# MCU.net
KiCad netlist of a schematic drawn in Altium Designer
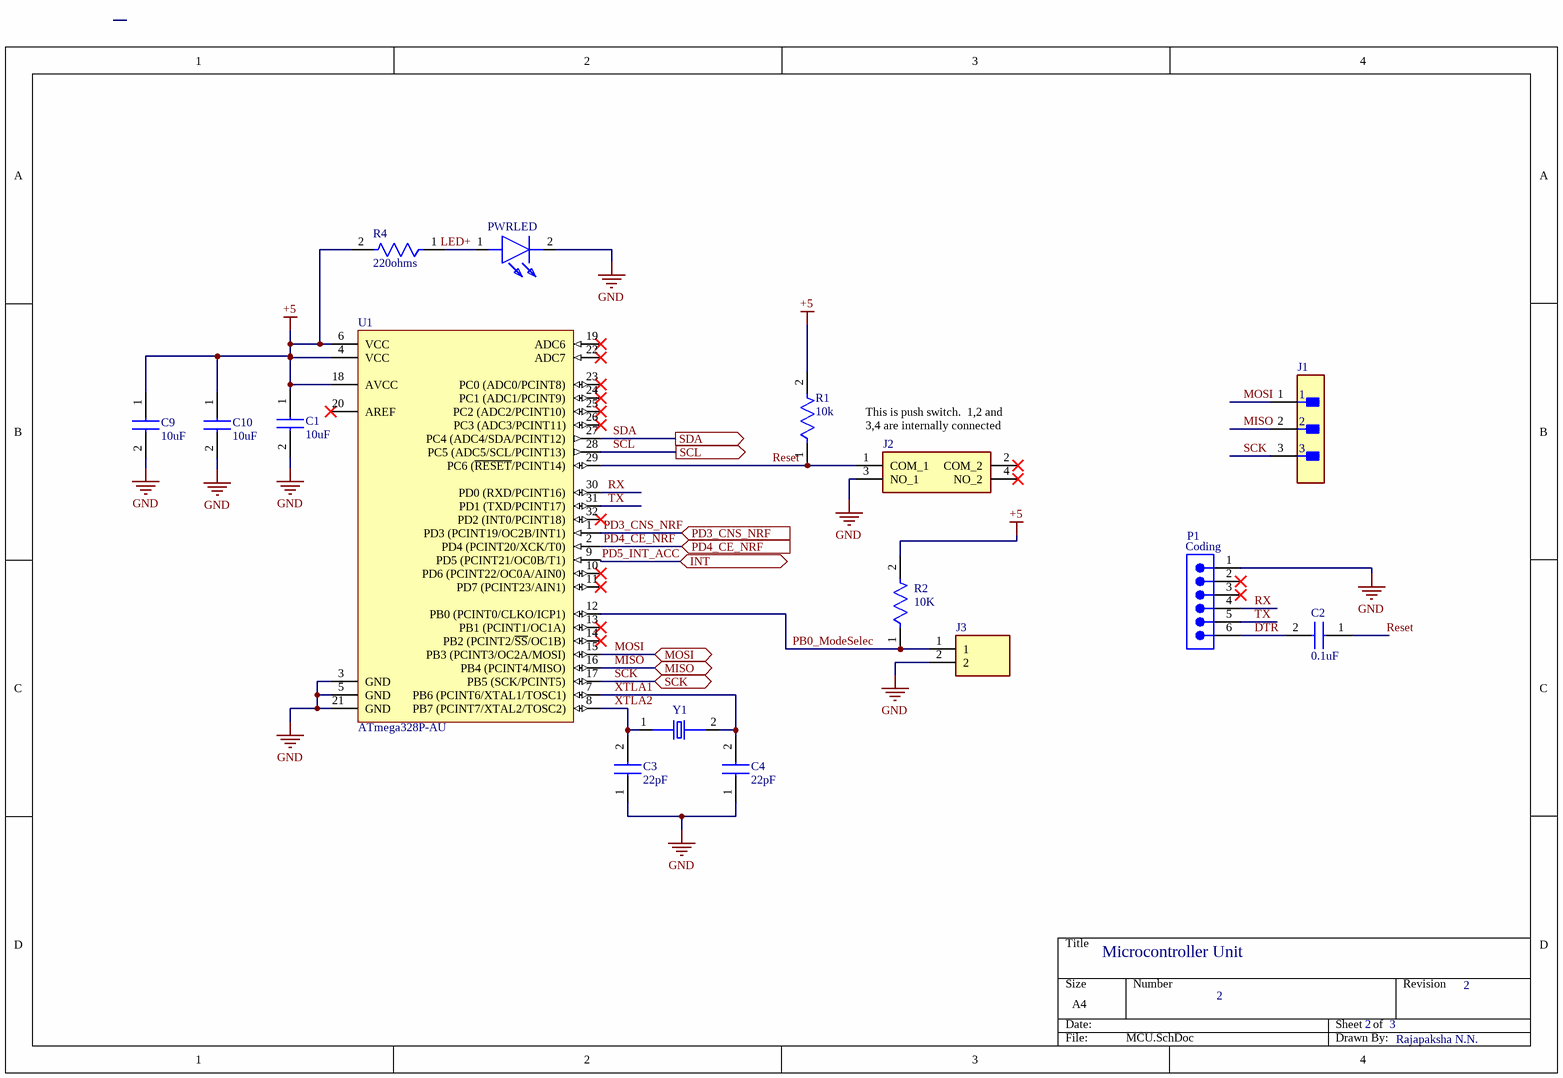
[diagram p0: MCU.SchDoc]

(export (version "E")
  (design (tool "Eeschema 10.0.6"))
  (components
    (comp (ref "C1")
      (value "10uF")
      (footprint "SamacSys:CAPC3216X180N")
      (description "Capacitor")
      (fields
        (field (name "MANUFACTURER_PART_NUMBER") "GRT31CR71E106KE13L")
        (field (name "MOUSER PART NUMBER") "81-GRT31CR71E106KE3L")
      )
      (libsource (lib "*") (part "GRT31CR71E106KE13L"))
    )
    (comp (ref "C2")
      (value "0.1uF")
      (footprint "SamacSys:C0805")
      (description "Capacitor")
      (fields
        (field (name "MANUFACTURER_PART_NUMBER") "C0805R104J5RACTU")
        (field (name "MOUSER PART NUMBER") "80-C0805R104J5RACTU")
      )
      (libsource (lib "*") (part "C0805R104J5RACTU"))
    )
    (comp (ref "C3")
      (value "22pF")
      (footprint "SamacSys:C0805")
      (description "Capacitor")
      (fields
        (field (name "MANUFACTURER_PART_NUMBER") "C0805C220F1HACTU")
        (field (name "MOUSER PART NUMBER") "80-C0805C220F1HACTU")
      )
      (libsource (lib "*") (part "C0805C220F1HACTU"))
    )
    (comp (ref "C4")
      (value "22pF")
      (footprint "SamacSys:C0805")
      (description "Capacitor")
      (fields
        (field (name "MANUFACTURER_PART_NUMBER") "C0805C220F1HACTU")
        (field (name "MOUSER PART NUMBER") "80-C0805C220F1HACTU")
      )
      (libsource (lib "*") (part "C0805C220F1HACTU"))
    )
    (comp (ref "C9")
      (value "10uF")
      (footprint "SamacSys:CAPC3216X180N")
      (description "Capacitor")
      (fields
        (field (name "MANUFACTURER_PART_NUMBER") "GRT31CR71E106KE13L")
        (field (name "MOUSER PART NUMBER") "81-GRT31CR71E106KE3L")
      )
      (libsource (lib "*") (part "GRT31CR71E106KE13L"))
    )
    (comp (ref "C10")
      (value "10uF")
      (footprint "SamacSys:CAPC3216X180N")
      (description "Capacitor")
      (fields
        (field (name "MANUFACTURER_PART_NUMBER") "GRT31CR71E106KE13L")
        (field (name "MOUSER PART NUMBER") "81-GRT31CR71E106KE3L")
      )
      (libsource (lib "*") (part "GRT31CR71E106KE13L"))
    )
    (comp (ref "J1")
      (value "87224-3")
      (footprint "FP-87224-3-MFG")
      (description "CONN HEADER VERT 3POS 2.54MM")
      (libsource (lib "Altium Content Vault") (part "0d3f023dd272f625e17a2be33dea85f"))
    )
    (comp (ref "J2")
      (value "8-1437565-1")
      (footprint "SamacSys:814375651")
      (description "Connector")
      (fields (field (name "MOUSER PART NUMBER") "506-8-1437565-1"))
      (libsource (lib "*") (part "8-1437565-1"))
    )
    (comp (ref "J3")
      (value "1727010")
      (footprint "SamacSys:1727010")
      (description "Connector")
      (fields (field (name "MOUSER PART NUMBER") "651-1727010"))
      (libsource (lib "*") (part "1727010"))
    )
    (comp (ref "P1")
      (value "Coding")
      (footprint "SMTC-TSW-106-07-X-S")
      (description "0.025\" SQ Post Header, Through-hole, Vertical, -55 to 125 degC, 2.54 mm Pitch, 6-Pin, Male, RoHS")
      (fields (field (name "PARTNUMBER") "TSW-106-07-L-S") (field (name "MANUFACTURER") "Samtec"))
      (libsource (lib "Altium Content Vault") (part "SMTC-TSW-106-X-X-S-X"))
    )
    (comp (ref "PWRLED")
      (value "598-2105-107F")
      (footprint "SamacSys:5982105107F")
      (description "LED")
      (fields (field (name "MOUSER PART NUMBER") "645-598-2105-107F"))
      (libsource (lib "*") (part "598-2105-107F"))
    )
    (comp (ref "R1")
      (value "10k")
      (footprint "FP-RK73H2A-IPC_C")
      (description "10kΩ ±1% 0.25W Chip Resistor 0805 Thick Film AEC-Q200 Qualified")
      (fields (field (name "TOLERANCE") "1%"))
      (libsource (lib "Altium Content Vault") (part "1029c3af85768c4190bb7ad29bc67b5"))
    )
    (comp (ref "R2")
      (value "10K")
      (footprint "FP-RK73H2A-IPC_C")
      (description "10kΩ ±1% 0.25W Chip Resistor 0805 Thick Film AEC-Q200 Qualified")
      (fields (field (name "TOLERANCE") "1%") (field (name "Comment") "10k"))
      (libsource (lib "Altium Content Vault") (part "1029c3af85768c4190bb7ad29bc67b5"))
    )
    (comp (ref "R4")
      (value "220ohms")
      (footprint "FP-RK73H2A-IPC_C")
      (description "10kΩ ±1% 0.25W Chip Resistor 0805 Thick Film AEC-Q200 Qualified")
      (fields (field (name "TOLERANCE") "1%"))
      (libsource (lib "Altium Content Vault") (part "1029c3af85768c4190bb7ad29bc67b5"))
    )
    (comp (ref "U1")
      (value "ATmega328P-AU")
      (footprint "32A_M")
      (libsource (lib "Altium Content Vault") (part "MC-8B-ATM48-SQ32"))
    )
    (comp (ref "Y1")
      (value "FOXSDLF/160-20")
      (footprint "XTAL_FOXSDLF/160-20")
      (description "Microprocessor, Crystal; 16 Mhz; + 30 Ppm @ Degc; 7 Pf (Max.); 20 Pf; -20 Deg")
      (fields (field (name "MF") "Fox Electronics"))
      (libsource (lib "FOXSDLF_160-20 (2)") (part "FOXSDLF/160-20"))
    )
  )
  (nets
    (net (code "1") (name "+5") (class "Default")
      (node (ref "C1") (pin "1") (pinfunction "1_1") (pintype "passive"))
      (node (ref "C10") (pin "1") (pinfunction "1_1") (pintype "passive"))
      (node (ref "C9") (pin "1") (pinfunction "1_1") (pintype "passive"))
      (node (ref "R1") (pin "2") (pinfunction "2_2") (pintype "passive"))
      (node (ref "R2") (pin "2") (pinfunction "2_2") (pintype "passive"))
      (node (ref "R4") (pin "2") (pinfunction "2_2") (pintype "passive"))
      (node (ref "U1") (pin "18") (pinfunction "AVCC_18") (pintype "power_in"))
      (node (ref "U1") (pin "4") (pinfunction "VCC_4") (pintype "power_in"))
      (node (ref "U1") (pin "6") (pinfunction "VCC_6") (pintype "power_in"))
    )
    (net (code "2") (name "/DTR") (class "Default")
      (node (ref "C2") (pin "2") (pinfunction "2_2") (pintype "passive"))
      (node (ref "P1") (pin "6") (pinfunction "6_6") (pintype "passive"))
    )
    (net (code "4") (name "/MISO") (class "Default")
      (node (ref "J1") (pin "2") (pinfunction "2_2") (pintype "passive"))
      (node (ref "U1") (pin "16") (pinfunction "PB4_(PCINT4/MISO)_16") (pintype "bidirectional"))
    )
    (net (code "5") (name "/MOSI") (class "Default")
      (node (ref "J1") (pin "1") (pinfunction "1_1") (pintype "passive"))
      (node (ref "U1") (pin "15") (pinfunction "PB3_(PCINT3/OC2A/MOSI)_15") (pintype "bidirectional"))
    )
    (net (code "6") (name "/PB0_ModeSelec") (class "Default")
      (node (ref "J3") (pin "1") (pinfunction "1_1") (pintype "passive"))
      (node (ref "R2") (pin "1") (pinfunction "1_1") (pintype "passive"))
      (node (ref "U1") (pin "12") (pinfunction "PB0_(PCINT0/CLKO/ICP1)_12") (pintype "bidirectional"))
    )
    (net (code "7") (name "/PD3_CNS_NRF") (class "Default")
      (node (ref "U1") (pin "1") (pinfunction "PD3_(PCINT19/OC2B/INT1)_1") (pintype "input"))
    )
    (net (code "8") (name "/PD4_CE_NRF") (class "Default")
      (node (ref "U1") (pin "2") (pinfunction "PD4_(PCINT20/XCK/T0)_2") (pintype "input"))
    )
    (net (code "9") (name "/PD5_INT_ACC") (class "Default")
      (node (ref "U1") (pin "9") (pinfunction "PD5_(PCINT21/OC0B/T1)_9") (pintype "input"))
    )
    (net (code "10") (name "/RX") (class "Default")
      (node (ref "P1") (pin "4") (pinfunction "4_4") (pintype "passive"))
      (node (ref "U1") (pin "30") (pinfunction "PD0_(RXD/PCINT16)_30") (pintype "bidirectional"))
    )
    (net (code "11") (name "/Reset") (class "Default")
      (node (ref "C2") (pin "1") (pinfunction "1_1") (pintype "passive"))
      (node (ref "J2") (pin "1") (pinfunction "COM_1_1") (pintype "passive"))
      (node (ref "R1") (pin "1") (pinfunction "1_1") (pintype "passive"))
      (node (ref "U1") (pin "29") (pinfunction "PC6_(~{RESET}/PCINT14)_29") (pintype "bidirectional"))
    )
    (net (code "12") (name "/SCK") (class "Default")
      (node (ref "J1") (pin "3") (pinfunction "3_3") (pintype "passive"))
      (node (ref "U1") (pin "17") (pinfunction "PB5_(SCK/PCINT5)_17") (pintype "bidirectional"))
    )
    (net (code "13") (name "/SCL") (class "Default")
      (node (ref "U1") (pin "28") (pinfunction "PC5_(ADC5/SCL/PCINT13)_28") (pintype "output"))
    )
    (net (code "14") (name "/SDA") (class "Default")
      (node (ref "U1") (pin "27") (pinfunction "PC4_(ADC4/SDA/PCINT12)_27") (pintype "output"))
    )
    (net (code "15") (name "/TX") (class "Default")
      (node (ref "P1") (pin "5") (pinfunction "5_5") (pintype "passive"))
      (node (ref "U1") (pin "31") (pinfunction "PD1_(TXD/PCINT17)_31") (pintype "bidirectional"))
    )
    (net (code "16") (name "/XTLA1") (class "Default")
      (node (ref "C4") (pin "2") (pinfunction "2_2") (pintype "passive"))
      (node (ref "U1") (pin "7") (pinfunction "PB6_(PCINT6/XTAL1/TOSC1)_7") (pintype "bidirectional"))
      (node (ref "Y1") (pin "2") (pinfunction "2_2") (pintype "passive"))
    )
    (net (code "17") (name "/XTLA2") (class "Default")
      (node (ref "C3") (pin "2") (pinfunction "2_2") (pintype "passive"))
      (node (ref "U1") (pin "8") (pinfunction "PB7_(PCINT7/XTAL2/TOSC2)_8") (pintype "bidirectional"))
      (node (ref "Y1") (pin "1") (pinfunction "1_1") (pintype "passive"))
    )
    (net (code "18") (name "GND") (class "Default")
      (node (ref "C1") (pin "2") (pinfunction "2_2") (pintype "passive"))
      (node (ref "C10") (pin "2") (pinfunction "2_2") (pintype "passive"))
      (node (ref "C3") (pin "1") (pinfunction "1_1") (pintype "passive"))
      (node (ref "C4") (pin "1") (pinfunction "1_1") (pintype "passive"))
      (node (ref "C9") (pin "2") (pinfunction "2_2") (pintype "passive"))
      (node (ref "J2") (pin "3") (pinfunction "NO_1_3") (pintype "passive"))
      (node (ref "J3") (pin "2") (pinfunction "2_2") (pintype "passive"))
      (node (ref "P1") (pin "1") (pinfunction "1_1") (pintype "passive"))
      (node (ref "PWRLED") (pin "2") (pinfunction "K_2") (pintype "passive"))
      (node (ref "U1") (pin "21") (pinfunction "GND_21") (pintype "power_in"))
      (node (ref "U1") (pin "3") (pinfunction "GND_3") (pintype "power_in"))
      (node (ref "U1") (pin "5") (pinfunction "GND_5") (pintype "power_in"))
    )
    (net (code "19") (name "Net-(PWRLED-A)") (class "Default")
      (node (ref "PWRLED") (pin "1") (pinfunction "A_1") (pintype "passive"))
      (node (ref "R4") (pin "1") (pinfunction "1_1") (pintype "passive"))
    )
    (net (code "20") (name "unconnected-(J2-COM_2-Pad2)") (class "Default")
      (node (ref "J2") (pin "2") (pinfunction "COM_2_2") (pintype "passive+no_connect"))
    )
    (net (code "21") (name "unconnected-(J2-NO_2-Pad4)") (class "Default")
      (node (ref "J2") (pin "4") (pinfunction "NO_2_4") (pintype "passive+no_connect"))
    )
    (net (code "22") (name "unconnected-(P1-Pad2)") (class "Default")
      (node (ref "P1") (pin "2") (pinfunction "2_2") (pintype "passive+no_connect"))
    )
    (net (code "23") (name "unconnected-(P1-Pad3)") (class "Default")
      (node (ref "P1") (pin "3") (pinfunction "3_3") (pintype "passive+no_connect"))
    )
    (net (code "24") (name "unconnected-(U1-ADC6-Pad19)") (class "Default")
      (node (ref "U1") (pin "19") (pinfunction "ADC6_19") (pintype "input+no_connect"))
    )
    (net (code "25") (name "unconnected-(U1-ADC7-Pad22)") (class "Default")
      (node (ref "U1") (pin "22") (pinfunction "ADC7_22") (pintype "input+no_connect"))
    )
    (net (code "26") (name "unconnected-(U1-AREF-Pad20)") (class "Default")
      (node (ref "U1") (pin "20") (pinfunction "AREF_20") (pintype "passive+no_connect"))
    )
    (net (code "27") (name "unconnected-(U1-PB1_(PCINT1{slash}OC1A)-Pad13)") (class "Default")
      (node (ref "U1") (pin "13") (pinfunction "PB1_(PCINT1/OC1A)_13") (pintype "bidirectional+no_connect"))
    )
    (net (code "28") (name "unconnected-(U1-PB2_(PCINT2{slash}~{SS}{slash}OC1B)-Pad14)") (class "Default")
      (node (ref "U1") (pin "14") (pinfunction "PB2_(PCINT2/~{SS}/OC1B)_14") (pintype "bidirectional+no_connect"))
    )
    (net (code "29") (name "unconnected-(U1-PC0_(ADC0{slash}PCINT8)-Pad23)") (class "Default")
      (node (ref "U1") (pin "23") (pinfunction "PC0_(ADC0/PCINT8)_23") (pintype "bidirectional+no_connect"))
    )
    (net (code "30") (name "unconnected-(U1-PC1_(ADC1{slash}PCINT9)-Pad24)") (class "Default")
      (node (ref "U1") (pin "24") (pinfunction "PC1_(ADC1/PCINT9)_24") (pintype "bidirectional+no_connect"))
    )
    (net (code "31") (name "unconnected-(U1-PC2_(ADC2{slash}PCINT10)-Pad25)") (class "Default")
      (node (ref "U1") (pin "25") (pinfunction "PC2_(ADC2/PCINT10)_25") (pintype "bidirectional+no_connect"))
    )
    (net (code "32") (name "unconnected-(U1-PC3_(ADC3{slash}PCINT11)-Pad26)") (class "Default")
      (node (ref "U1") (pin "26") (pinfunction "PC3_(ADC3/PCINT11)_26") (pintype "bidirectional+no_connect"))
    )
    (net (code "33") (name "unconnected-(U1-PD2_(INT0{slash}PCINT18)-Pad32)") (class "Default")
      (node (ref "U1") (pin "32") (pinfunction "PD2_(INT0/PCINT18)_32") (pintype "bidirectional+no_connect"))
    )
    (net (code "34") (name "unconnected-(U1-PD6_(PCINT22{slash}OC0A{slash}AIN0)-Pad10)") (class "Default")
      (node (ref "U1") (pin "10") (pinfunction "PD6_(PCINT22/OC0A/AIN0)_10") (pintype "bidirectional+no_connect"))
    )
    (net (code "35") (name "unconnected-(U1-PD7_(PCINT23{slash}AIN1)-Pad11)") (class "Default")
      (node (ref "U1") (pin "11") (pinfunction "PD7_(PCINT23/AIN1)_11") (pintype "bidirectional+no_connect"))
    )
  )
)
